# GSM.net
KiCad netlist of a schematic drawn in Altium Designer
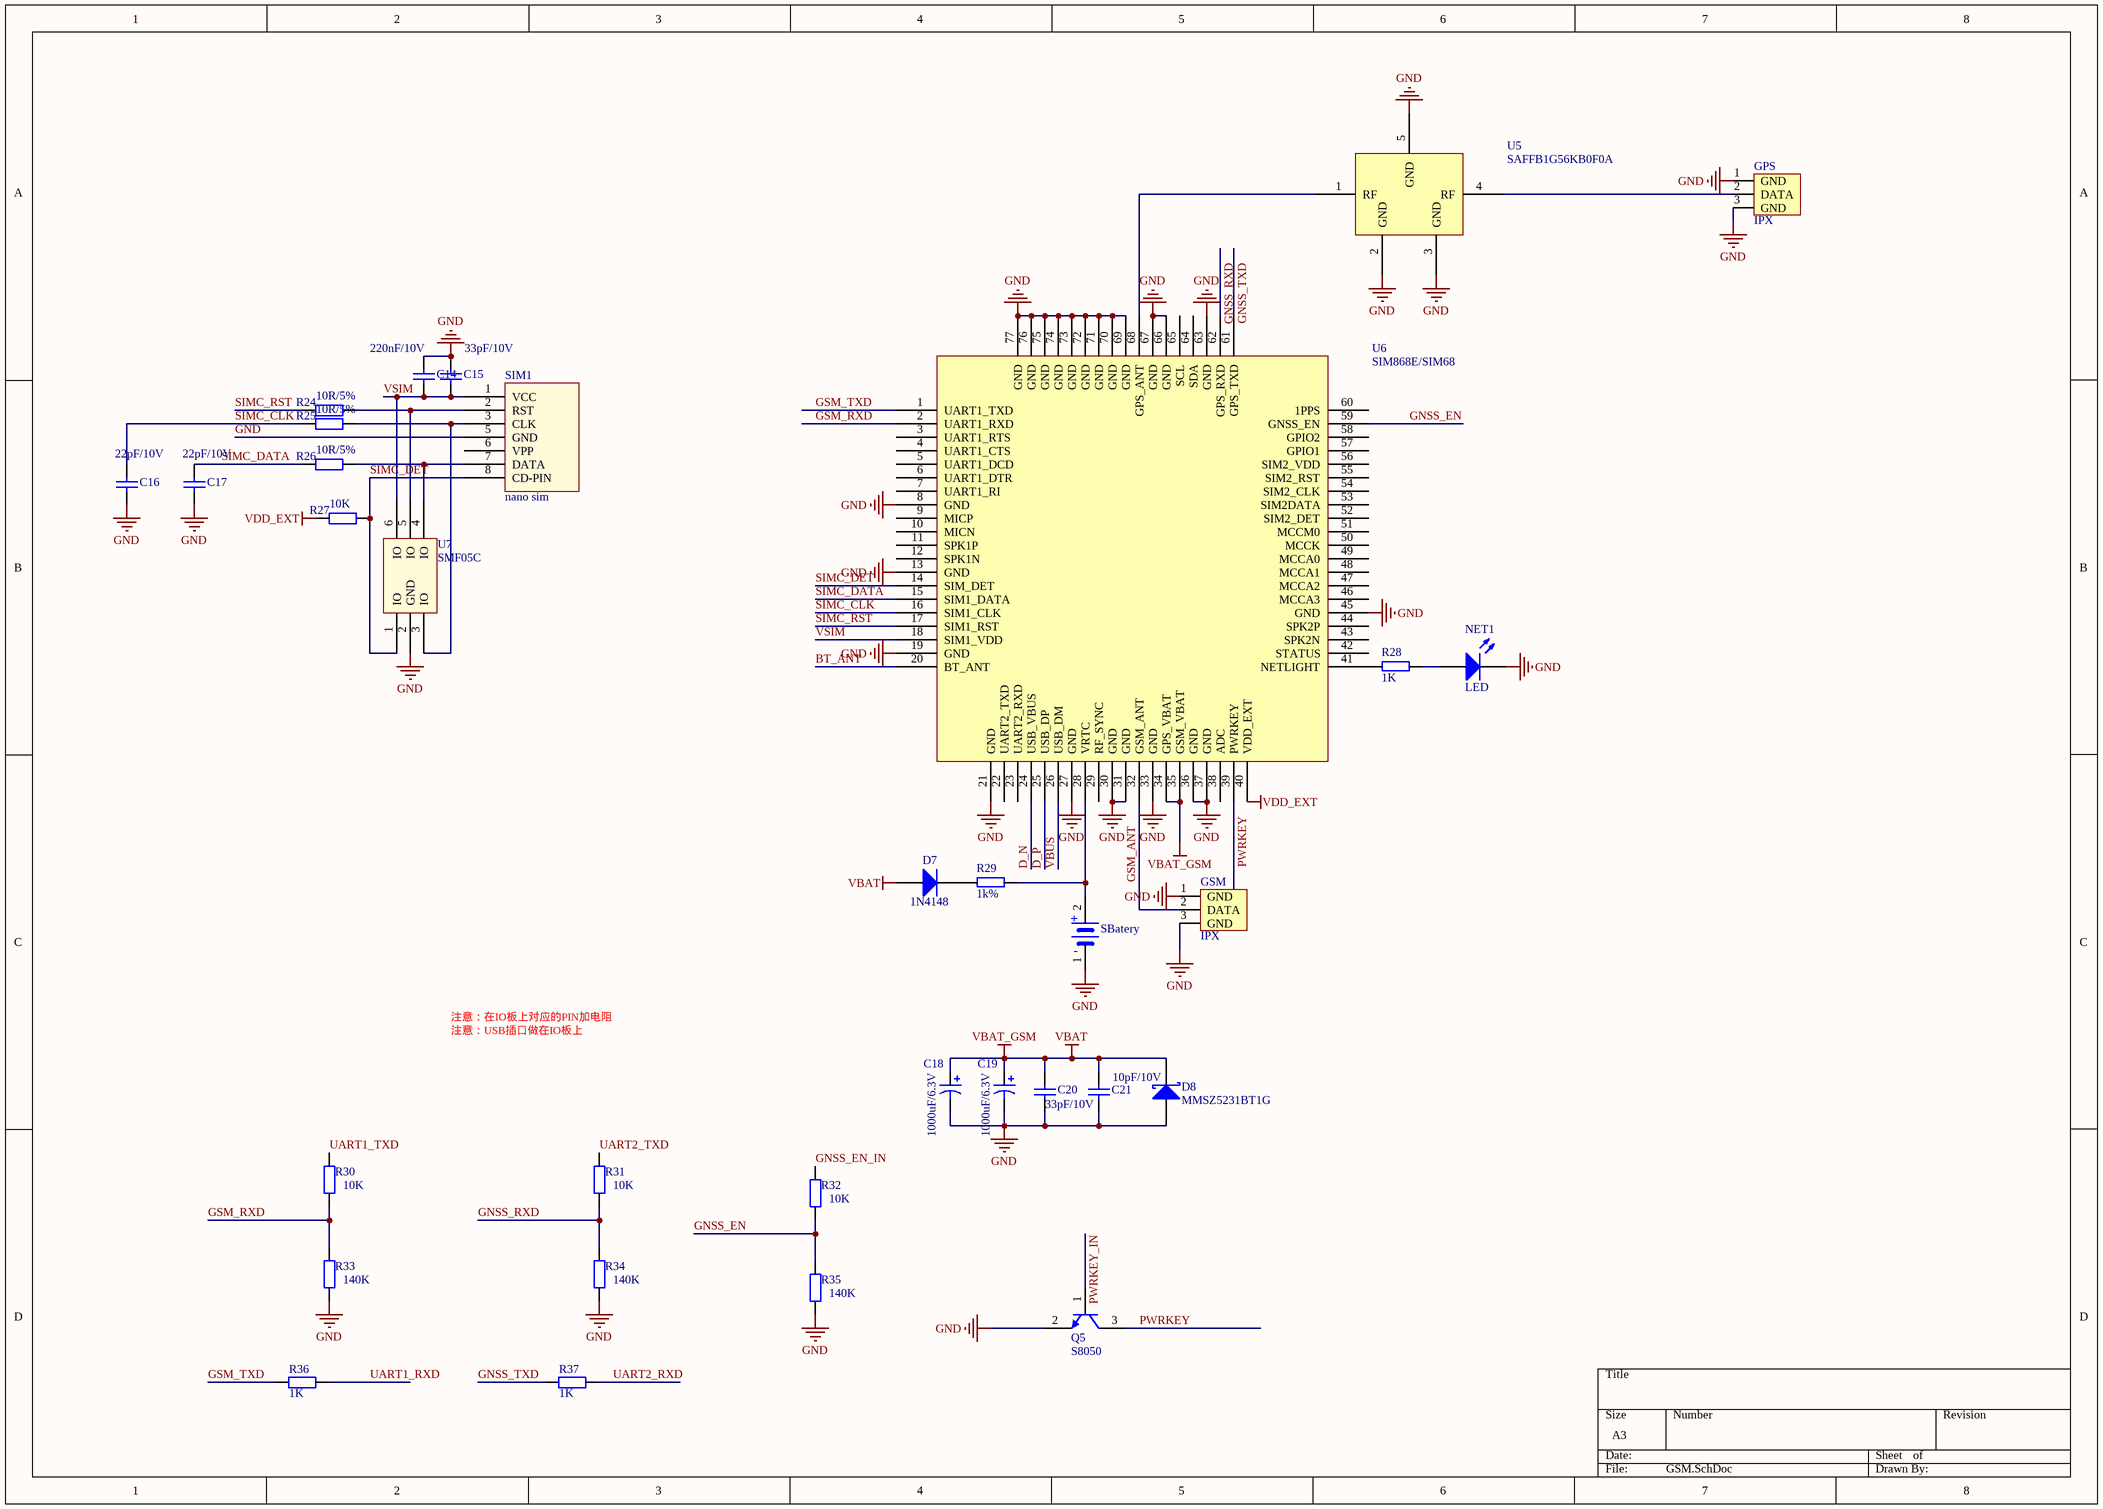
[diagram p0: GSM.SchDoc]

(export (version "E")
  (design (tool "Eeschema 10.0.6"))
  (components
    (comp (ref "C14")
      (value "220nF/10V")
      (footprint "0402C")
      (description "Capacitor")
      (fields (field (name "PUBLISHER") "Altium Limited"))
      (libsource (lib "Miscellaneous Devices") (part "Cap"))
    )
    (comp (ref "C15")
      (value "33pF/10V")
      (footprint "0402C")
      (description "Capacitor")
      (fields (field (name "PUBLISHER") "Altium Limited"))
      (libsource (lib "Miscellaneous Devices") (part "Cap"))
    )
    (comp (ref "C16")
      (value "22pF/10V")
      (footprint "0402C")
      (description "Capacitor")
      (fields (field (name "PUBLISHER") "Altium Limited"))
      (libsource (lib "Miscellaneous Devices") (part "Cap"))
    )
    (comp (ref "C17")
      (value "22pF/10V")
      (footprint "0402C")
      (description "Capacitor")
      (fields (field (name "PUBLISHER") "Altium Limited"))
      (libsource (lib "Miscellaneous Devices") (part "Cap"))
    )
    (comp (ref "C18")
      (value "1000uF/6.3V")
      (footprint "7343")
      (description "Polarized Capacitor (Radial)")
      (fields (field (name "PUBLISHER") "Altium Limited"))
      (libsource (lib "Miscellaneous Devices") (part "Cap Pol1"))
    )
    (comp (ref "C19")
      (value "1000uF/6.3V")
      (footprint "7343")
      (description "Polarized Capacitor (Radial)")
      (fields (field (name "PUBLISHER") "Altium Limited"))
      (libsource (lib "Miscellaneous Devices") (part "Cap Pol1"))
    )
    (comp (ref "C20")
      (value "33pF/10V")
      (footprint "0402C")
      (description "Capacitor")
      (fields (field (name "PUBLISHER") "Altium Limited"))
      (libsource (lib "Miscellaneous Devices") (part "Cap"))
    )
    (comp (ref "C21")
      (value "10pF/10V")
      (footprint "0402C")
      (description "Capacitor")
      (fields (field (name "PUBLISHER") "Altium Limited"))
      (libsource (lib "Miscellaneous Devices") (part "Cap"))
    )
    (comp (ref "D7")
      (value "1N4148")
      (footprint "sod323")
      (description "High Conductance Fast Diode")
      (fields (field (name "PUBLISHER") "Altium Limited"))
      (libsource (lib "Miscellaneous Devices") (part "Diode 1N4148"))
    )
    (comp (ref "D8")
      (value "MMSZ5231BT1G")
      (footprint "SOD123")
      (description "Schottky Rectifier")
      (fields (field (name "PUBLISHER") "Altium Limited"))
      (libsource (lib "Miscellaneous Devices") (part "Diode 10TQ040"))
    )
    (comp (ref "GPS")
      (value "IPX")
      (footprint "IPX")
      (description "IPEX座")
      (libsource (lib "SIM800C 原理图库") (part "IPEX"))
    )
    (comp (ref "GSM")
      (value "IPX")
      (footprint "IPX")
      (description "IPEX座")
      (libsource (lib "SIM800C 原理图库") (part "IPEX"))
    )
    (comp (ref "NET1")
      (value "LED")
      (footprint "0603LED")
      (description "Typical RED, GREEN, YELLOW, AMBER GaAs LED")
      (fields (field (name "PUBLISHER") "Altium Limited"))
      (libsource (lib "SIM800C 原理图库") (part "LED2"))
    )
    (comp (ref "Q5") (value "S8050") (footprint "SOT23-3") (libsource (lib "Schlib1") (part "NPN")))
    (comp (ref "R24")
      (value "10R/5%")
      (footprint "0402R")
      (description "Resistor")
      (fields (field (name "PUBLISHER") "Altium Limited"))
      (libsource (lib "") (part "Res2_1"))
    )
    (comp (ref "R25")
      (value "10R/5%")
      (footprint "0402R")
      (description "Resistor")
      (fields (field (name "PUBLISHER") "Altium Limited"))
      (libsource (lib "") (part "Res2_1"))
    )
    (comp (ref "R26")
      (value "10R/5%")
      (footprint "0402R")
      (description "Resistor")
      (fields (field (name "PUBLISHER") "Altium Limited"))
      (libsource (lib "") (part "Res2_1"))
    )
    (comp (ref "R27")
      (value "10K")
      (footprint "0402R")
      (description "Resistor")
      (fields (field (name "PUBLISHER") "Altium Limited"))
      (libsource (lib "") (part "Res2_1"))
    )
    (comp (ref "R28") (value "1K") (footprint "0402R") (libsource (lib "SIM800C 原理图库") (part "R")))
    (comp (ref "R29") (value "1k%") (footprint "0402R") (libsource (lib "SIM800C 原理图库") (part "R")))
    (comp (ref "R30")
      (value "10K")
      (footprint "0402R")
      (description "Resistor")
      (fields (field (name "PUBLISHER") "Altium Limited"))
      (libsource (lib "Miscellaneous Devices") (part "Res2"))
    )
    (comp (ref "R31")
      (value "10K")
      (footprint "0402R")
      (description "Resistor")
      (fields (field (name "PUBLISHER") "Altium Limited"))
      (libsource (lib "Miscellaneous Devices") (part "Res2"))
    )
    (comp (ref "R32")
      (value "10K")
      (footprint "0402R")
      (description "Resistor")
      (fields (field (name "PUBLISHER") "Altium Limited"))
      (libsource (lib "Miscellaneous Devices") (part "Res2"))
    )
    (comp (ref "R33")
      (value "140K")
      (footprint "0402R")
      (description "Resistor")
      (fields (field (name "PUBLISHER") "Altium Limited"))
      (libsource (lib "Miscellaneous Devices") (part "Res2"))
    )
    (comp (ref "R34")
      (value "140K")
      (footprint "0402R")
      (description "Resistor")
      (fields (field (name "PUBLISHER") "Altium Limited"))
      (libsource (lib "Miscellaneous Devices") (part "Res2"))
    )
    (comp (ref "R35")
      (value "140K")
      (footprint "0402R")
      (description "Resistor")
      (fields (field (name "PUBLISHER") "Altium Limited"))
      (libsource (lib "Miscellaneous Devices") (part "Res2"))
    )
    (comp (ref "R36")
      (value "1K")
      (footprint "0402R")
      (description "Resistor")
      (fields (field (name "PUBLISHER") "Altium Limited"))
      (libsource (lib "") (part "Res2_2"))
    )
    (comp (ref "R37")
      (value "1K")
      (footprint "0402R")
      (description "Resistor")
      (fields (field (name "PUBLISHER") "Altium Limited"))
      (libsource (lib "") (part "Res2_2"))
    )
    (comp (ref "SBatery")
      (value "SBatery")
      (footprint "MS621FE")
      (libsource (lib "Myself_1") (part "SBatery"))
    )
    (comp (ref "SIM1") (value "nano sim") (footprint "Nano SIM") (libsource (lib "lm") (part "nano sim")))
    (comp (ref "U5")
      (value "SAFFB1G56KB0F0A")
      (footprint "SAFFB1G56KB0F0A")
      (libsource (lib "stm32") (part "SAFFB1G56KBOFA"))
    )
    (comp (ref "U6")
      (value "SIM868E/SIM68")
      (footprint "SIM868")
      (libsource (lib "stm32") (part "SIM868E/SIM868"))
    )
    (comp (ref "U7") (value "SMF05C") (footprint "SC70-6L") (libsource (lib "lm") (part "SMF05C")))
  )
  (nets
    (net (code "1") (name "/BT_ANT") (class "Default")
      (node (ref "U6") (pin "20") (pinfunction "BT_ANT_20") (pintype "passive"))
    )
    (net (code "2") (name "/D_N") (class "Default")
      (node (ref "U6") (pin "24") (pinfunction "USB_VBUS_24") (pintype "passive"))
    )
    (net (code "3") (name "/D_P") (class "Default")
      (node (ref "U6") (pin "25") (pinfunction "USB_DP_25") (pintype "passive"))
    )
    (net (code "4") (name "/GNSS_EN") (class "Default")
      (node (ref "R32") (pin "2") (pinfunction "2_2") (pintype "passive"))
      (node (ref "R35") (pin "1") (pinfunction "1_1") (pintype "passive"))
      (node (ref "U6") (pin "59") (pinfunction "GNSS_EN_59") (pintype "passive"))
    )
    (net (code "5") (name "/GNSS_EN_IN") (class "Default")
      (node (ref "R32") (pin "1") (pinfunction "1_1") (pintype "passive"))
    )
    (net (code "6") (name "/GNSS_RXD") (class "Default")
      (node (ref "R31") (pin "2") (pinfunction "2_2") (pintype "passive"))
      (node (ref "R34") (pin "1") (pinfunction "1_1") (pintype "passive"))
      (node (ref "U6") (pin "62") (pinfunction "GPS_RXD_62") (pintype "passive"))
    )
    (net (code "7") (name "/GNSS_TXD") (class "Default")
      (node (ref "R37") (pin "1") (pinfunction "1_1") (pintype "passive"))
      (node (ref "U6") (pin "61") (pinfunction "GPS_TXD_61") (pintype "passive"))
    )
    (net (code "8") (name "/GSM_ANT") (class "Default")
      (node (ref "GSM") (pin "2") (pinfunction "DATA_2") (pintype "passive"))
      (node (ref "U6") (pin "32") (pinfunction "GSM_ANT_32") (pintype "passive"))
    )
    (net (code "9") (name "/GSM_RXD") (class "Default")
      (node (ref "R30") (pin "2") (pinfunction "2_2") (pintype "passive"))
      (node (ref "R33") (pin "1") (pinfunction "1_1") (pintype "passive"))
      (node (ref "U6") (pin "2") (pinfunction "UART1_RXD_2") (pintype "passive"))
    )
    (net (code "10") (name "/GSM_TXD") (class "Default")
      (node (ref "R36") (pin "1") (pinfunction "1_1") (pintype "passive"))
      (node (ref "U6") (pin "1") (pinfunction "UART1_TXD_1") (pintype "passive"))
    )
    (net (code "11") (name "/PWRKEY") (class "Default")
      (node (ref "Q5") (pin "3") (pinfunction "C_3") (pintype "passive"))
      (node (ref "U6") (pin "39") (pinfunction "PWRKEY_39") (pintype "passive"))
    )
    (net (code "12") (name "/PWRKEY_IN") (class "Default")
      (node (ref "Q5") (pin "1") (pinfunction "B_1") (pintype "passive"))
    )
    (net (code "13") (name "/SIMC_CLK") (class "Default")
      (node (ref "C16") (pin "1") (pinfunction "1_1") (pintype "passive"))
      (node (ref "R25") (pin "2") (pinfunction "2_2") (pintype "passive"))
      (node (ref "U6") (pin "16") (pinfunction "SIM1_CLK_16") (pintype "passive"))
    )
    (net (code "14") (name "/SIMC_DATA") (class "Default")
      (node (ref "C17") (pin "1") (pinfunction "1_1") (pintype "passive"))
      (node (ref "R26") (pin "2") (pinfunction "2_2") (pintype "passive"))
      (node (ref "U6") (pin "15") (pinfunction "SIM1_DATA_15") (pintype "passive"))
    )
    (net (code "15") (name "/SIMC_DET") (class "Default")
      (node (ref "R27") (pin "1") (pinfunction "1_1") (pintype "passive"))
      (node (ref "SIM1") (pin "8") (pinfunction "CD-PIN_8") (pintype "passive"))
      (node (ref "U6") (pin "14") (pinfunction "SIM_DET_14") (pintype "passive"))
      (node (ref "U7") (pin "1") (pinfunction "IO_1") (pintype "passive"))
    )
    (net (code "16") (name "/SIMC_RST") (class "Default")
      (node (ref "R24") (pin "2") (pinfunction "2_2") (pintype "passive"))
      (node (ref "U6") (pin "17") (pinfunction "SIM1_RST_17") (pintype "passive"))
    )
    (net (code "17") (name "/UART1_RXD") (class "Default")
      (node (ref "R36") (pin "2") (pinfunction "2_2") (pintype "passive"))
    )
    (net (code "18") (name "/UART1_TXD") (class "Default")
      (node (ref "R30") (pin "1") (pinfunction "1_1") (pintype "passive"))
    )
    (net (code "19") (name "/UART2_RXD") (class "Default")
      (node (ref "R37") (pin "2") (pinfunction "2_2") (pintype "passive"))
    )
    (net (code "20") (name "/UART2_TXD") (class "Default")
      (node (ref "R31") (pin "1") (pinfunction "1_1") (pintype "passive"))
    )
    (net (code "21") (name "/VBUS") (class "Default")
      (node (ref "U6") (pin "26") (pinfunction "USB_DM_26") (pintype "passive"))
    )
    (net (code "22") (name "/VSIM") (class "Default")
      (node (ref "C14") (pin "2") (pinfunction "2_2") (pintype "passive"))
      (node (ref "C15") (pin "2") (pinfunction "2_2") (pintype "passive"))
      (node (ref "SIM1") (pin "1") (pinfunction "VCC_1") (pintype "passive"))
      (node (ref "U6") (pin "18") (pinfunction "SIM1_VDD_18") (pintype "passive"))
      (node (ref "U7") (pin "6") (pinfunction "IO_6") (pintype "passive"))
    )
    (net (code "23") (name "GND") (class "Default")
      (node (ref "C14") (pin "1") (pinfunction "1_1") (pintype "passive"))
      (node (ref "C15") (pin "1") (pinfunction "1_1") (pintype "passive"))
      (node (ref "C16") (pin "2") (pinfunction "2_2") (pintype "passive"))
      (node (ref "C17") (pin "2") (pinfunction "2_2") (pintype "passive"))
      (node (ref "C18") (pin "2") (pinfunction "2_2") (pintype "passive"))
      (node (ref "C19") (pin "2") (pinfunction "2_2") (pintype "passive"))
      (node (ref "C20") (pin "2") (pinfunction "2_2") (pintype "passive"))
      (node (ref "C21") (pin "2") (pinfunction "2_2") (pintype "passive"))
      (node (ref "D8") (pin "A") (pinfunction "A_A") (pintype "passive"))
      (node (ref "GPS") (pin "1") (pinfunction "GND_1") (pintype "passive"))
      (node (ref "GPS") (pin "3") (pinfunction "GND_3") (pintype "passive"))
      (node (ref "GSM") (pin "1") (pinfunction "GND_1") (pintype "passive"))
      (node (ref "GSM") (pin "3") (pinfunction "GND_3") (pintype "passive"))
      (node (ref "NET1") (pin "2") (pinfunction "K_2") (pintype "passive"))
      (node (ref "Q5") (pin "2") (pinfunction "E_2") (pintype "passive"))
      (node (ref "R33") (pin "2") (pinfunction "2_2") (pintype "passive"))
      (node (ref "R34") (pin "2") (pinfunction "2_2") (pintype "passive"))
      (node (ref "R35") (pin "2") (pinfunction "2_2") (pintype "passive"))
      (node (ref "SBatery") (pin "1") (pinfunction "1_1") (pintype "passive"))
      (node (ref "SIM1") (pin "5") (pinfunction "GND_5") (pintype "passive"))
      (node (ref "U5") (pin "2") (pinfunction "GND_2") (pintype "passive"))
      (node (ref "U5") (pin "3") (pinfunction "GND_3") (pintype "passive"))
      (node (ref "U5") (pin "5") (pinfunction "GND_5") (pintype "passive"))
      (node (ref "U6") (pin "13") (pinfunction "GND_13") (pintype "passive"))
      (node (ref "U6") (pin "19") (pinfunction "GND_19") (pintype "passive"))
      (node (ref "U6") (pin "21") (pinfunction "GND_21") (pintype "passive"))
      (node (ref "U6") (pin "27") (pinfunction "GND_27") (pintype "passive"))
      (node (ref "U6") (pin "30") (pinfunction "GND_30") (pintype "passive"))
      (node (ref "U6") (pin "31") (pinfunction "GND_31") (pintype "passive"))
      (node (ref "U6") (pin "33") (pinfunction "GND_33") (pintype "passive"))
      (node (ref "U6") (pin "36") (pinfunction "GND_36") (pintype "passive"))
      (node (ref "U6") (pin "37") (pinfunction "GND_37") (pintype "passive"))
      (node (ref "U6") (pin "45") (pinfunction "GND_45") (pintype "passive"))
      (node (ref "U6") (pin "63") (pinfunction "GND_63") (pintype "passive"))
      (node (ref "U6") (pin "66") (pinfunction "GND_66") (pintype "passive"))
      (node (ref "U6") (pin "67") (pinfunction "GND_67") (pintype "passive"))
      (node (ref "U6") (pin "69") (pinfunction "GND_69") (pintype "passive"))
      (node (ref "U6") (pin "70") (pinfunction "GND_70") (pintype "passive"))
      (node (ref "U6") (pin "71") (pinfunction "GND_71") (pintype "passive"))
      (node (ref "U6") (pin "72") (pinfunction "GND_72") (pintype "passive"))
      (node (ref "U6") (pin "73") (pinfunction "GND_73") (pintype "passive"))
      (node (ref "U6") (pin "74") (pinfunction "GND_74") (pintype "passive"))
      (node (ref "U6") (pin "75") (pinfunction "GND_75") (pintype "passive"))
      (node (ref "U6") (pin "76") (pinfunction "GND_76") (pintype "passive"))
      (node (ref "U6") (pin "77") (pinfunction "GND_77") (pintype "passive"))
      (node (ref "U6") (pin "8") (pinfunction "GND_8") (pintype "passive"))
      (node (ref "U7") (pin "2") (pinfunction "GND_2") (pintype "passive"))
    )
    (net (code "24") (name "Net-(D7-K)") (class "Default")
      (node (ref "D7") (pin "2") (pinfunction "K_2") (pintype "passive"))
      (node (ref "R29") (pin "2") (pintype "passive"))
    )
    (net (code "25") (name "Net-(GPS-DATA)") (class "Default")
      (node (ref "GPS") (pin "2") (pinfunction "DATA_2") (pintype "passive"))
      (node (ref "U5") (pin "4") (pinfunction "RF_4") (pintype "passive"))
    )
    (net (code "26") (name "Net-(NET1-A)") (class "Default")
      (node (ref "NET1") (pin "1") (pinfunction "A_1") (pintype "passive"))
      (node (ref "R28") (pin "1") (pintype "passive"))
    )
    (net (code "27") (name "Net-(SIM1-CLK)") (class "Default")
      (node (ref "R25") (pin "1") (pinfunction "1_1") (pintype "passive"))
      (node (ref "SIM1") (pin "3") (pinfunction "CLK_3") (pintype "passive"))
      (node (ref "U7") (pin "3") (pinfunction "IO_3") (pintype "passive"))
    )
    (net (code "28") (name "Net-(SIM1-DATA)") (class "Default")
      (node (ref "R26") (pin "1") (pinfunction "1_1") (pintype "passive"))
      (node (ref "SIM1") (pin "7") (pinfunction "DATA_7") (pintype "passive"))
      (node (ref "U7") (pin "4") (pinfunction "IO_4") (pintype "passive"))
    )
    (net (code "29") (name "Net-(SIM1-RST)") (class "Default")
      (node (ref "R24") (pin "1") (pinfunction "1_1") (pintype "passive"))
      (node (ref "SIM1") (pin "2") (pinfunction "RST_2") (pintype "passive"))
      (node (ref "U7") (pin "5") (pinfunction "IO_5") (pintype "passive"))
    )
    (net (code "30") (name "Net-(U6-GPS_ANT)") (class "Default")
      (node (ref "U5") (pin "1") (pinfunction "RF_1") (pintype "passive"))
      (node (ref "U6") (pin "68") (pinfunction "GPS_ANT_68") (pintype "passive"))
    )
    (net (code "31") (name "Net-(U6-NETLIGHT)") (class "Default")
      (node (ref "R28") (pin "2") (pintype "passive"))
      (node (ref "U6") (pin "41") (pinfunction "NETLIGHT_41") (pintype "passive"))
    )
    (net (code "32") (name "Net-(U6-VRTC)") (class "Default")
      (node (ref "R29") (pin "1") (pintype "passive"))
      (node (ref "SBatery") (pin "2") (pinfunction "2_2") (pintype "passive"))
      (node (ref "U6") (pin "28") (pinfunction "VRTC_28") (pintype "passive"))
    )
    (net (code "33") (name "VBAT") (class "Default")
      (node (ref "C18") (pin "1") (pinfunction "1_1") (pintype "passive"))
      (node (ref "C19") (pin "1") (pinfunction "1_1") (pintype "passive"))
      (node (ref "C20") (pin "1") (pinfunction "1_1") (pintype "passive"))
      (node (ref "C21") (pin "1") (pinfunction "1_1") (pintype "passive"))
      (node (ref "D7") (pin "1") (pinfunction "A_1") (pintype "passive"))
      (node (ref "D8") (pin "K") (pinfunction "K_K") (pintype "passive"))
      (node (ref "U6") (pin "34") (pinfunction "GPS_VBAT_34") (pintype "passive"))
      (node (ref "U6") (pin "35") (pinfunction "GSM_VBAT_35") (pintype "passive"))
    )
    (net (code "34") (name "VDD_EXT") (class "Default")
      (node (ref "R27") (pin "2") (pinfunction "2_2") (pintype "passive"))
      (node (ref "U6") (pin "40") (pinfunction "VDD_EXT_40") (pintype "passive"))
    )
    (net (code "35") (name "unconnected-(SIM1-VPP-Pad6)") (class "Default")
      (node (ref "SIM1") (pin "6") (pinfunction "VPP_6") (pintype "passive"))
    )
    (net (code "36") (name "unconnected-(U6-1PPS-Pad60)") (class "Default")
      (node (ref "U6") (pin "60") (pinfunction "1PPS_60") (pintype "passive"))
    )
    (net (code "37") (name "unconnected-(U6-ADC-Pad38)") (class "Default")
      (node (ref "U6") (pin "38") (pinfunction "ADC_38") (pintype "passive"))
    )
    (net (code "38") (name "unconnected-(U6-GPIO1-Pad57)") (class "Default")
      (node (ref "U6") (pin "57") (pinfunction "GPIO1_57") (pintype "passive"))
    )
    (net (code "39") (name "unconnected-(U6-GPIO2-Pad58)") (class "Default")
      (node (ref "U6") (pin "58") (pinfunction "GPIO2_58") (pintype "passive"))
    )
    (net (code "40") (name "unconnected-(U6-MCCA0-Pad49)") (class "Default")
      (node (ref "U6") (pin "49") (pinfunction "MCCA0_49") (pintype "passive"))
    )
    (net (code "41") (name "unconnected-(U6-MCCA1-Pad48)") (class "Default")
      (node (ref "U6") (pin "48") (pinfunction "MCCA1_48") (pintype "passive"))
    )
    (net (code "42") (name "unconnected-(U6-MCCA2-Pad47)") (class "Default")
      (node (ref "U6") (pin "47") (pinfunction "MCCA2_47") (pintype "passive"))
    )
    (net (code "43") (name "unconnected-(U6-MCCA3-Pad46)") (class "Default")
      (node (ref "U6") (pin "46") (pinfunction "MCCA3_46") (pintype "passive"))
    )
    (net (code "44") (name "unconnected-(U6-MCCK-Pad50)") (class "Default")
      (node (ref "U6") (pin "50") (pinfunction "MCCK_50") (pintype "passive"))
    )
    (net (code "45") (name "unconnected-(U6-MCCM0-Pad51)") (class "Default")
      (node (ref "U6") (pin "51") (pinfunction "MCCM0_51") (pintype "passive"))
    )
    (net (code "46") (name "unconnected-(U6-MICN-Pad10)") (class "Default")
      (node (ref "U6") (pin "10") (pinfunction "MICN_10") (pintype "passive"))
    )
    (net (code "47") (name "unconnected-(U6-MICP-Pad9)") (class "Default")
      (node (ref "U6") (pin "9") (pinfunction "MICP_9") (pintype "passive"))
    )
    (net (code "48") (name "unconnected-(U6-RF_SYNC-Pad29)") (class "Default")
      (node (ref "U6") (pin "29") (pinfunction "RF_SYNC_29") (pintype "passive"))
    )
    (net (code "49") (name "unconnected-(U6-SCL-Pad65)") (class "Default")
      (node (ref "U6") (pin "65") (pinfunction "SCL_65") (pintype "passive"))
    )
    (net (code "50") (name "unconnected-(U6-SDA-Pad64)") (class "Default")
      (node (ref "U6") (pin "64") (pinfunction "SDA_64") (pintype "passive"))
    )
    (net (code "51") (name "unconnected-(U6-SIM2DATA-Pad53)") (class "Default")
      (node (ref "U6") (pin "53") (pinfunction "SIM2DATA_53") (pintype "passive"))
    )
    (net (code "52") (name "unconnected-(U6-SIM2_CLK-Pad54)") (class "Default")
      (node (ref "U6") (pin "54") (pinfunction "SIM2_CLK_54") (pintype "passive"))
    )
    (net (code "53") (name "unconnected-(U6-SIM2_DET-Pad52)") (class "Default")
      (node (ref "U6") (pin "52") (pinfunction "SIM2_DET_52") (pintype "passive"))
    )
    (net (code "54") (name "unconnected-(U6-SIM2_RST-Pad55)") (class "Default")
      (node (ref "U6") (pin "55") (pinfunction "SIM2_RST_55") (pintype "passive"))
    )
    (net (code "55") (name "unconnected-(U6-SIM2_VDD-Pad56)") (class "Default")
      (node (ref "U6") (pin "56") (pinfunction "SIM2_VDD_56") (pintype "passive"))
    )
    (net (code "56") (name "unconnected-(U6-SPK1N-Pad12)") (class "Default")
      (node (ref "U6") (pin "12") (pinfunction "SPK1N_12") (pintype "passive"))
    )
    (net (code "57") (name "unconnected-(U6-SPK1P-Pad11)") (class "Default")
      (node (ref "U6") (pin "11") (pinfunction "SPK1P_11") (pintype "passive"))
    )
    (net (code "58") (name "unconnected-(U6-SPK2N-Pad43)") (class "Default")
      (node (ref "U6") (pin "43") (pinfunction "SPK2N_43") (pintype "passive"))
    )
    (net (code "59") (name "unconnected-(U6-SPK2P-Pad44)") (class "Default")
      (node (ref "U6") (pin "44") (pinfunction "SPK2P_44") (pintype "passive"))
    )
    (net (code "60") (name "unconnected-(U6-STATUS-Pad42)") (class "Default")
      (node (ref "U6") (pin "42") (pinfunction "STATUS_42") (pintype "passive"))
    )
    (net (code "61") (name "unconnected-(U6-UART1_CTS-Pad4)") (class "Default")
      (node (ref "U6") (pin "4") (pinfunction "UART1_CTS_4") (pintype "passive"))
    )
    (net (code "62") (name "unconnected-(U6-UART1_DCD-Pad5)") (class "Default")
      (node (ref "U6") (pin "5") (pinfunction "UART1_DCD_5") (pintype "passive"))
    )
    (net (code "63") (name "unconnected-(U6-UART1_DTR-Pad6)") (class "Default")
      (node (ref "U6") (pin "6") (pinfunction "UART1_DTR_6") (pintype "passive"))
    )
    (net (code "64") (name "unconnected-(U6-UART1_RI-Pad7)") (class "Default")
      (node (ref "U6") (pin "7") (pinfunction "UART1_RI_7") (pintype "passive"))
    )
    (net (code "65") (name "unconnected-(U6-UART1_RTS-Pad3)") (class "Default")
      (node (ref "U6") (pin "3") (pinfunction "UART1_RTS_3") (pintype "passive"))
    )
    (net (code "66") (name "unconnected-(U6-UART2_RXD-Pad23)") (class "Default")
      (node (ref "U6") (pin "23") (pinfunction "UART2_RXD_23") (pintype "passive"))
    )
    (net (code "67") (name "unconnected-(U6-UART2_TXD-Pad22)") (class "Default")
      (node (ref "U6") (pin "22") (pinfunction "UART2_TXD_22") (pintype "passive"))
    )
  )
)
